# ProPrj_PA_SWITCH_V4_2026-02-15.net
KiCad netlist of a schematic drawn in EasyEDA Pro
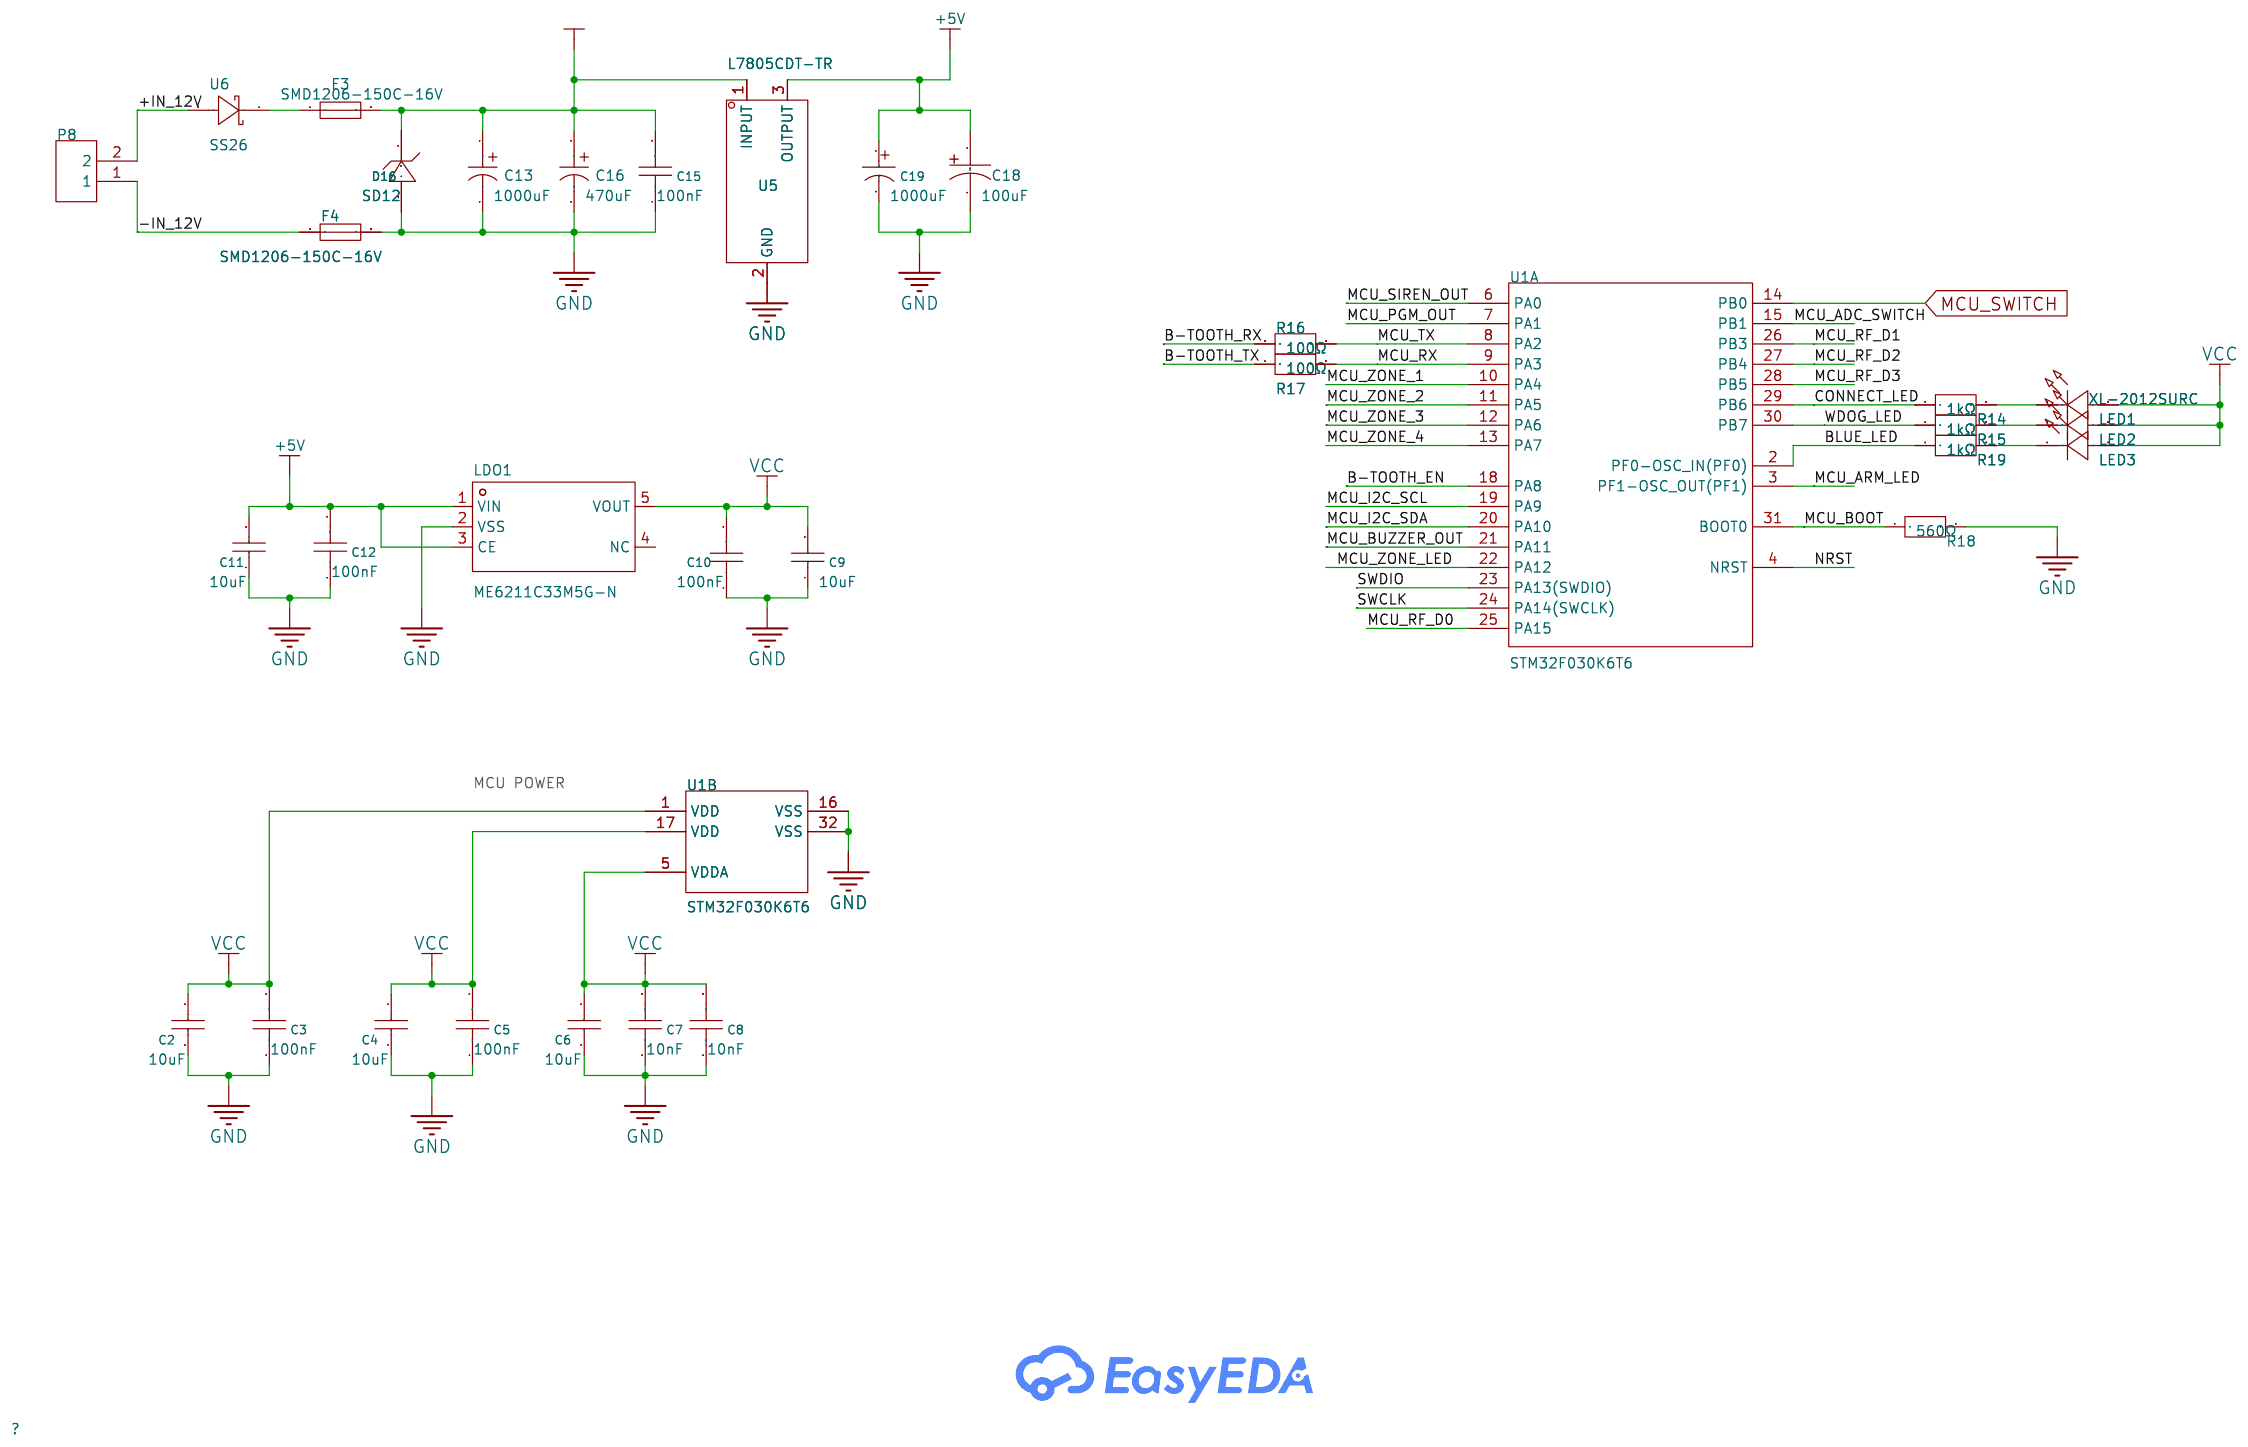
[diagram p0: MCU_POWER]
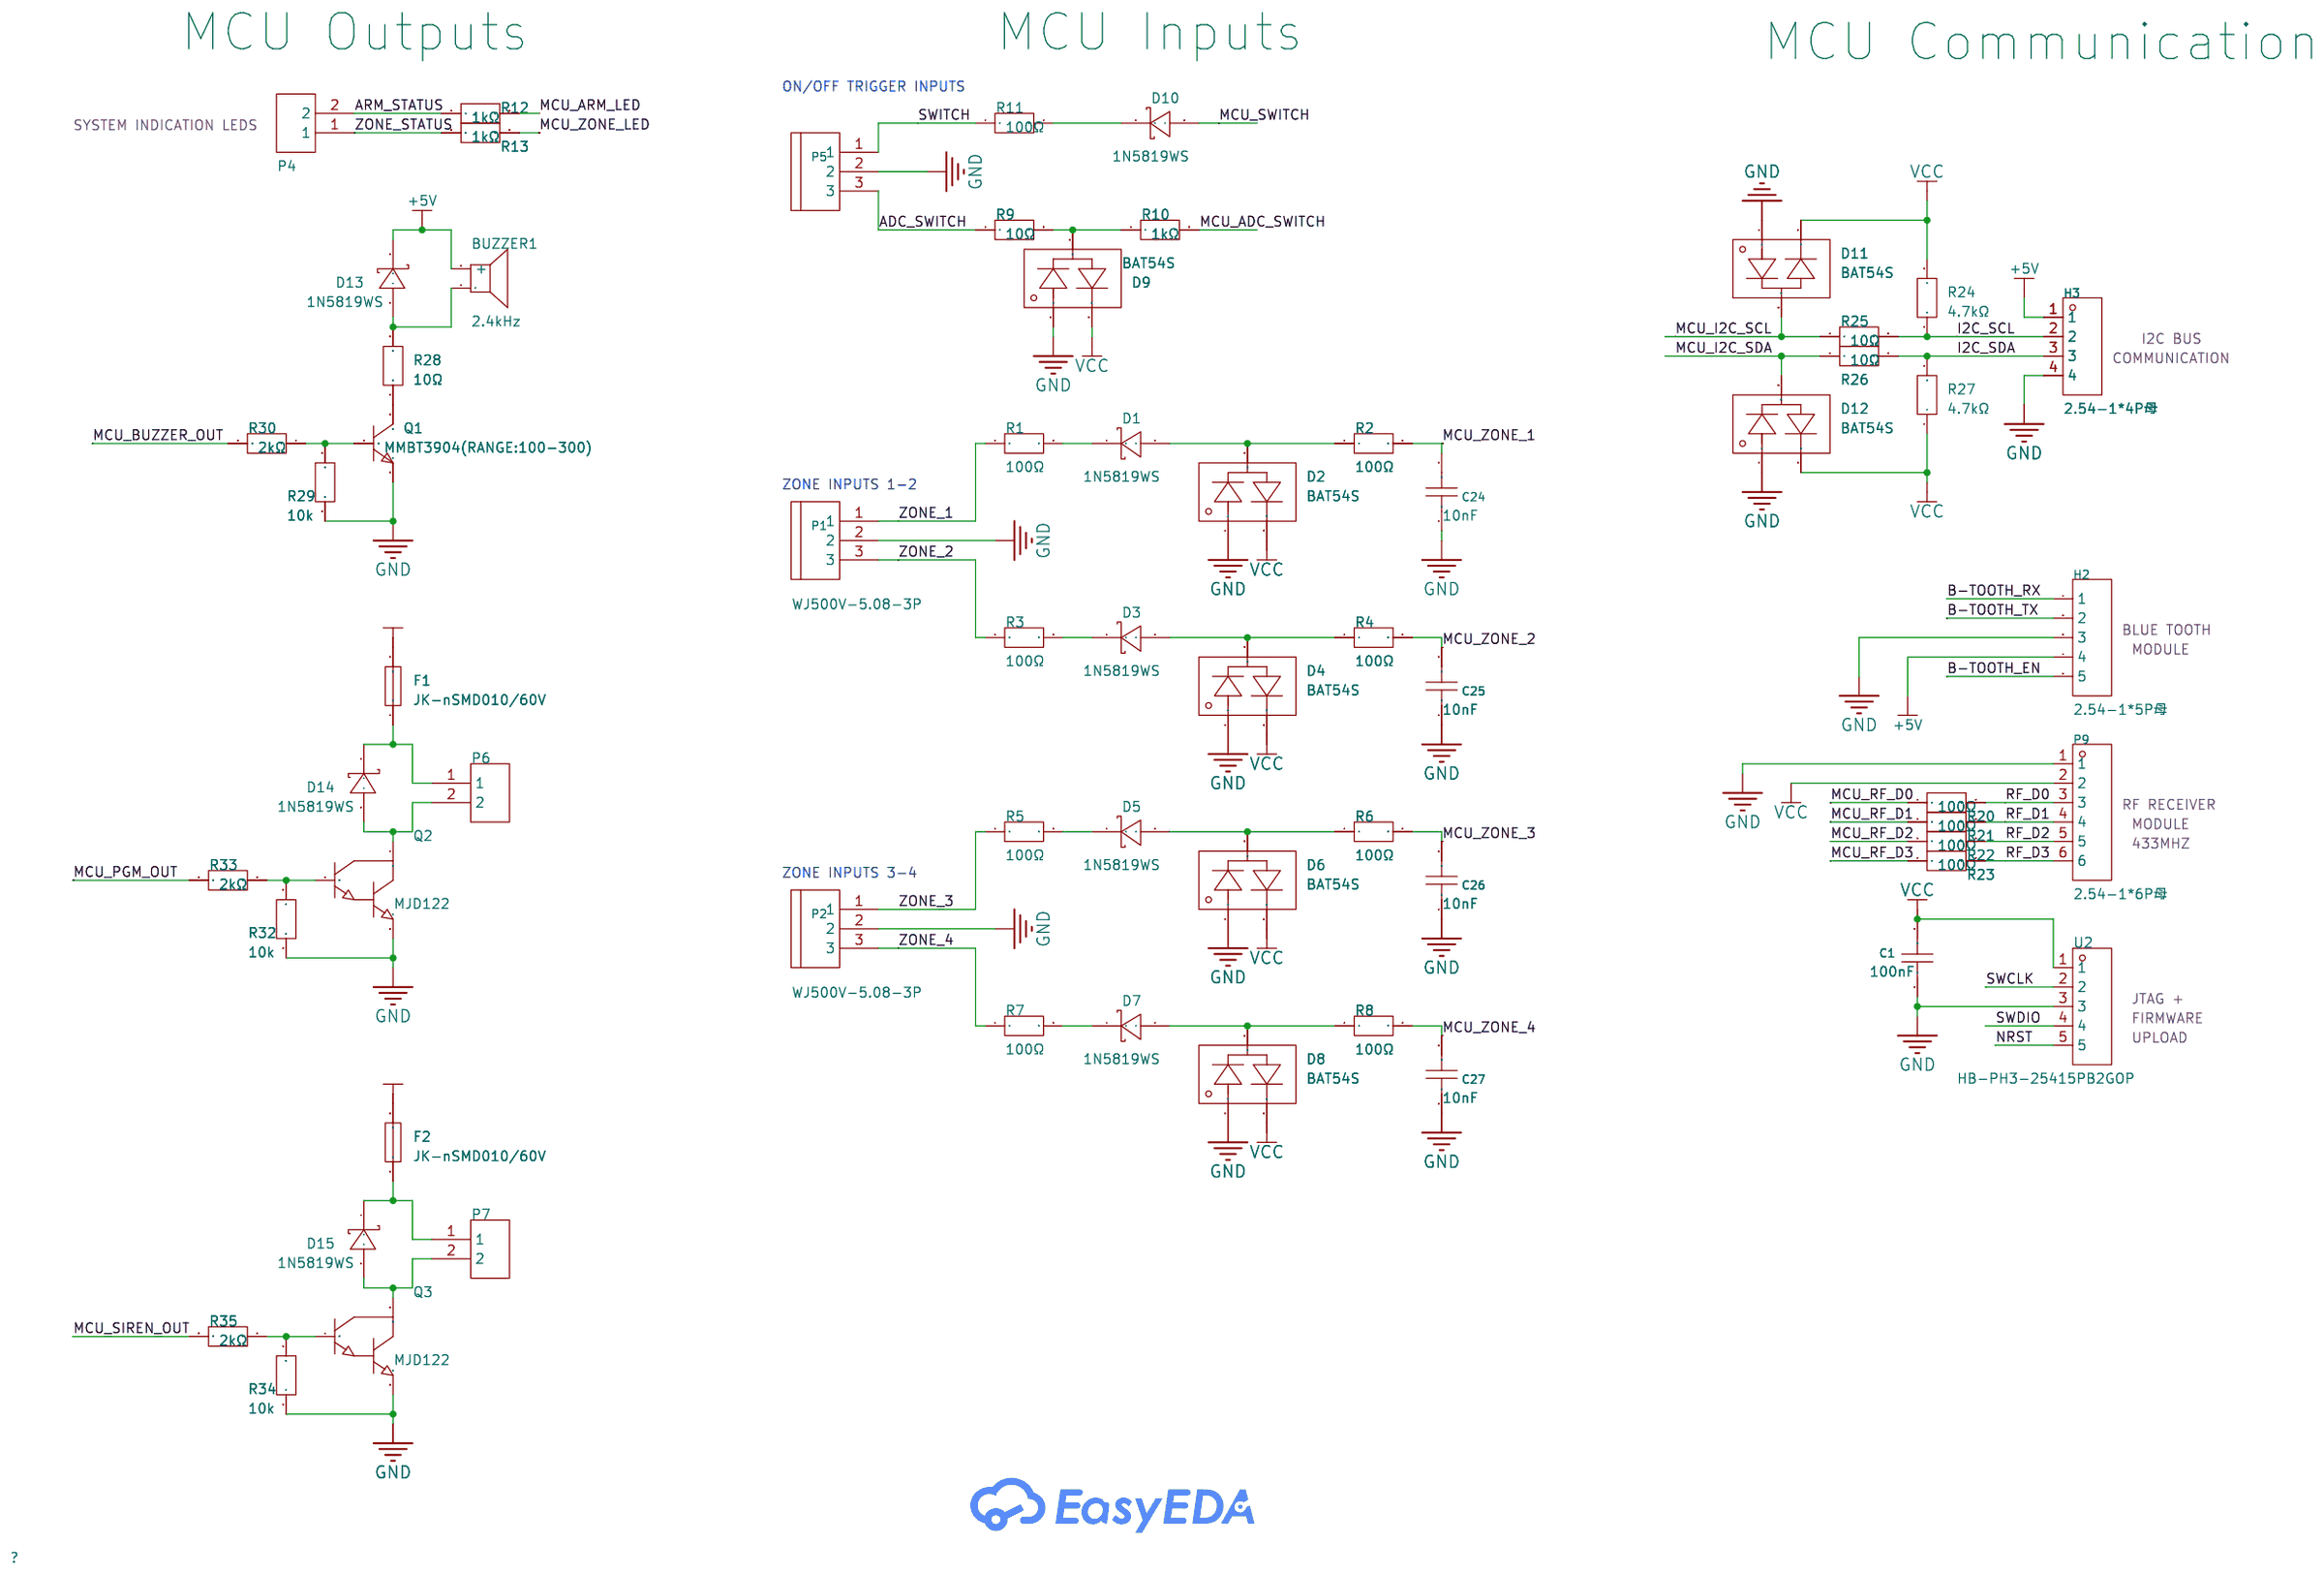
[diagram p1: INPUTS_OUTPUTS]

(export (version "E")
  (design (tool "Eeschema 10.0.6"))
  (components
    (comp (ref "C2")
      (value "10uF")
      (footprint "easyedapro:C0603")
      (fields
        (field (name "Manufacturer Part") "GRM188R60J106ME47D")
        (field (name "Manufacturer") "muRata(村田)")
      )
      (libsource (lib "easyedapro") (part "GRM188R60J106ME47D"))
    )
    (comp (ref "C3")
      (value "100nF")
      (footprint "easyedapro:C0603")
      (fields
        (field (name "Manufacturer Part") "CC0603KRX7R9BB104")
        (field (name "Manufacturer") "YAGEO(国巨)")
      )
      (libsource (lib "easyedapro") (part "CC0603KRX7R9BB104"))
    )
    (comp (ref "C4")
      (value "10uF")
      (footprint "easyedapro:C0603")
      (fields
        (field (name "Manufacturer Part") "GRM188R60J106ME47D")
        (field (name "Manufacturer") "muRata(村田)")
      )
      (libsource (lib "easyedapro") (part "GRM188R60J106ME47D"))
    )
    (comp (ref "C5")
      (value "100nF")
      (footprint "easyedapro:C0603")
      (fields
        (field (name "Manufacturer Part") "CC0603KRX7R9BB104")
        (field (name "Manufacturer") "YAGEO(国巨)")
      )
      (libsource (lib "easyedapro") (part "CC0603KRX7R9BB104"))
    )
    (comp (ref "C6")
      (value "10uF")
      (footprint "easyedapro:C0603")
      (fields
        (field (name "Manufacturer Part") "GRM188R60J106ME47D")
        (field (name "Manufacturer") "muRata(村田)")
      )
      (libsource (lib "easyedapro") (part "GRM188R60J106ME47D"))
    )
    (comp (ref "C7")
      (value "10nF")
      (footprint "easyedapro:C0603")
      (fields
        (field (name "Manufacturer Part") "CC0603KRX7R9BB104")
        (field (name "Manufacturer") "YAGEO(国巨)")
      )
      (libsource (lib "easyedapro") (part "CC0603KRX7R9BB104"))
    )
    (comp (ref "C8")
      (value "10nF")
      (footprint "easyedapro:C0603")
      (fields
        (field (name "Manufacturer Part") "CC0603KRX7R9BB104")
        (field (name "Manufacturer") "YAGEO(国巨)")
      )
      (libsource (lib "easyedapro") (part "CC0603KRX7R9BB104"))
    )
    (comp (ref "C9")
      (value "10uF")
      (footprint "easyedapro:C0603")
      (fields
        (field (name "Manufacturer Part") "GRM188R60J106ME47D")
        (field (name "Manufacturer") "muRata(村田)")
      )
      (libsource (lib "easyedapro") (part "GRM188R60J106ME47D"))
    )
    (comp (ref "C10")
      (value "100nF")
      (footprint "easyedapro:C0603")
      (fields
        (field (name "Manufacturer Part") "CC0603KRX7R9BB104")
        (field (name "Manufacturer") "YAGEO(国巨)")
      )
      (libsource (lib "easyedapro") (part "CC0603KRX7R9BB104"))
    )
    (comp (ref "C11")
      (value "10uF")
      (footprint "easyedapro:C0603")
      (fields
        (field (name "Manufacturer Part") "GRM188R60J106ME47D")
        (field (name "Manufacturer") "muRata(村田)")
      )
      (libsource (lib "easyedapro") (part "GRM188R60J106ME47D"))
    )
    (comp (ref "C12")
      (value "100nF")
      (footprint "easyedapro:C0603")
      (fields
        (field (name "Manufacturer Part") "CC0603KRX7R9BB104")
        (field (name "Manufacturer") "YAGEO(国巨)")
      )
      (libsource (lib "easyedapro") (part "CC0603KRX7R9BB104"))
    )
    (comp (ref "C13")
      (value "1000uF")
      (footprint "easyedapro:CAP-TH_BD10.0-P5.00-D0.6-FD")
      (fields
        (field (name "Manufacturer Part") "CD2881081EM1017VFL")
        (field (name "Manufacturer") "HRK(鸿瑞凯电子)")
      )
      (libsource (lib "easyedapro") (part "CD2881081EM1017VFL"))
    )
    (comp (ref "C15")
      (value "100nF")
      (footprint "easyedapro:C0603")
      (fields
        (field (name "Manufacturer Part") "CC0603KRX7R9BB104")
        (field (name "Manufacturer") "YAGEO(国巨)")
      )
      (libsource (lib "easyedapro") (part "CC0603KRX7R9BB104"))
    )
    (comp (ref "C16")
      (value "470uF")
      (footprint "easyedapro:CAP-TH_BD8.0-P3.50-D0.6-FD_1")
      (fields
        (field (name "Manufacturer Part") "CD2884771EM0812VFL")
        (field (name "Manufacturer") "HRK(鸿瑞凯电子)")
      )
      (libsource (lib "easyedapro") (part "CD2884771EM0812VFL"))
    )
    (comp (ref "C18")
      (value "100uF")
      (footprint "easyedapro:CAP-TH_BD5.0-P2.00-D0.8-FD")
      (fields
        (field (name "Manufacturer Part") "REA101M1ABK-0511P")
        (field (name "Manufacturer") "lelon(立隆)")
      )
      (libsource (lib "easyedapro") (part "REA101M1ABK-0511P"))
    )
    (comp (ref "C19")
      (value "1000uF")
      (footprint "easyedapro:CAP-TH_BD8.0-P3.50-D0.6-FD")
      (fields
        (field (name "Manufacturer Part") "GR108M010F12RR0VL4FP0")
        (field (name "Manufacturer") "CX(承兴)")
      )
      (libsource (lib "easyedapro") (part "1000uF 10V"))
    )
    (comp (ref "D16")
      (value "SD12")
      (footprint "easyedapro:SOD-323_L1.7-W1.3-LS2.7-RD")
      (fields (field (name "Manufacturer") "MDD"))
      (libsource (lib "easyedapro") (part "SD12"))
    )
    (comp (ref "F3")
      (value "SMD1206-150C-16V")
      (footprint "easyedapro:F1206")
      (fields (field (name "Manufacturer") "BNstar(比诺星)"))
      (libsource (lib "easyedapro") (part "SMD1206-150C-16V"))
    )
    (comp (ref "F4")
      (value "SMD1206-150C-16V")
      (footprint "easyedapro:F1206")
      (fields (field (name "Manufacturer") "BNstar(比诺星)"))
      (libsource (lib "easyedapro") (part "SMD1206-150C-16V"))
    )
    (comp (ref "LDO1")
      (value "ME6211C33M5G-N")
      (footprint "easyedapro:SOT-23-5_L3.0-W1.7-P0.95-LS2.8-BL")
      (fields (field (name "Manufacturer") "MICRONE(南京微盟)"))
      (libsource (lib "easyedapro") (part "ME6211C33M5G-N"))
    )
    (comp (ref "LED1")
      (value "XL-2012SURC")
      (footprint "easyedapro:LED0805-R-RD")
      (fields (field (name "Manufacturer") "XINGLIGHT(成兴光)"))
      (libsource (lib "easyedapro") (part "XL-2012SURC"))
    )
    (comp (ref "LED2")
      (value "XL-2012UGC")
      (footprint "easyedapro:LED0805-RD_GREEN")
      (fields (field (name "Manufacturer") "XINGLIGHT(成兴光)"))
      (libsource (lib "easyedapro") (part "XL-2012UGC"))
    )
    (comp (ref "LED3")
      (value "XL-2012UGC")
      (footprint "easyedapro:LED0805-RD_GREEN")
      (fields (field (name "Manufacturer") "XINGLIGHT(成兴光)"))
      (libsource (lib "easyedapro") (part "XL-2012UGC"))
    )
    (comp (ref "P8")
      (value "WJ500V-5.08-2P")
      (footprint "easyedapro:CONN-TH_2P-P5.00_WJ500V-5.08-2P")
      (fields (field (name "Manufacturer") "KANGNEX(康奈克斯电气)"))
      (libsource (lib "easyedapro") (part "WJ500V-5.08-2P-14-00A"))
    )
    (comp (ref "R14")
      (value "1kΩ")
      (footprint "easyedapro:R0603")
      (fields (field (name "Manufacturer Part") "SCR0603J1K") (field (name "Manufacturer") "VO(翔胜)"))
      (libsource (lib "easyedapro") (part "FRC0603J103TS"))
    )
    (comp (ref "R15")
      (value "1kΩ")
      (footprint "easyedapro:R0603")
      (fields (field (name "Manufacturer Part") "SCR0603J1K") (field (name "Manufacturer") "VO(翔胜)"))
      (libsource (lib "easyedapro") (part "FRC0603J103TS"))
    )
    (comp (ref "R16")
      (value "100Ω")
      (footprint "easyedapro:R0603")
      (fields (field (name "Manufacturer Part") "CR0603FA1000G") (field (name "Manufacturer") "LIZ(丽智电子)"))
      (libsource (lib "easyedapro") (part "FRC0603J103TS"))
    )
    (comp (ref "R17")
      (value "100Ω")
      (footprint "easyedapro:R0603")
      (fields (field (name "Manufacturer Part") "CR0603FA1000G") (field (name "Manufacturer") "LIZ(丽智电子)"))
      (libsource (lib "easyedapro") (part "FRC0603J103TS"))
    )
    (comp (ref "R18")
      (value "560Ω")
      (footprint "easyedapro:R0603")
      (fields (field (name "Manufacturer Part") "AECR0603F560RK9") (field (name "Manufacturer") "RESI(开步睿思)"))
      (libsource (lib "easyedapro") (part "FRC0603J103TS"))
    )
    (comp (ref "R19")
      (value "1kΩ")
      (footprint "easyedapro:R0603")
      (fields (field (name "Manufacturer Part") "SCR0603J1K") (field (name "Manufacturer") "VO(翔胜)"))
      (libsource (lib "easyedapro") (part "FRC0603J103TS"))
    )
    (comp (ref "U1")
      (value "STM32F030K6T6")
      (footprint "easyedapro:TQFP-32_L7.0-W7.0-P0.50-BL")
      (fields (field (name "Manufacturer") "ST(意法半导体)"))
      (libsource (lib "easyedapro") (part "STM32F030K6T6"))
    )
    (comp (ref "U5")
      (value "L7805CDT-TR")
      (footprint "easyedapro:TO-252-3_L6.5-W5.8-P4.58-BL")
      (fields (field (name "Manufacturer") "ST(意法半导体)"))
      (libsource (lib "easyedapro") (part "L7805CDT-TR"))
    )
    (comp (ref "U6")
      (value "SS26")
      (footprint "easyedapro:SMA_L4.3-W2.6-LS5.1-RD")
      (fields (field (name "Manufacturer") "ElecSuper(静芯微)"))
      (libsource (lib "easyedapro") (part "SS26_C5350986"))
    )
    (comp (ref "BUZZER1")
      (value "2.4kHz")
      (footprint "easyedapro:BUZ-TH_BD12.0-P7.60-D0.6-FD")
      (fields (field (name "Manufacturer Part") "TMB12A05") (field (name "Manufacturer") "华能"))
      (libsource (lib "easyedapro") (part "TMB12A05"))
    )
    (comp (ref "C1")
      (value "100nF")
      (footprint "easyedapro:C0603")
      (fields
        (field (name "Manufacturer Part") "CC0603KRX7R9BB104")
        (field (name "Manufacturer") "YAGEO(国巨)")
      )
      (libsource (lib "easyedapro") (part "CC0603KRX7R9BB104"))
    )
    (comp (ref "C24")
      (value "10nF")
      (footprint "easyedapro:C0603")
      (fields
        (field (name "Manufacturer Part") "CC0603KRX7R9BB104")
        (field (name "Manufacturer") "YAGEO(国巨)")
      )
      (libsource (lib "easyedapro") (part "CC0603KRX7R9BB104"))
    )
    (comp (ref "C25")
      (value "10nF")
      (footprint "easyedapro:C0603")
      (fields
        (field (name "Manufacturer Part") "CC0603KRX7R9BB104")
        (field (name "Manufacturer") "YAGEO(国巨)")
      )
      (libsource (lib "easyedapro") (part "CC0603KRX7R9BB104"))
    )
    (comp (ref "C26")
      (value "10nF")
      (footprint "easyedapro:C0603")
      (fields
        (field (name "Manufacturer Part") "CC0603KRX7R9BB104")
        (field (name "Manufacturer") "YAGEO(国巨)")
      )
      (libsource (lib "easyedapro") (part "CC0603KRX7R9BB104"))
    )
    (comp (ref "C27")
      (value "10nF")
      (footprint "easyedapro:C0603")
      (fields
        (field (name "Manufacturer Part") "CC0603KRX7R9BB104")
        (field (name "Manufacturer") "YAGEO(国巨)")
      )
      (libsource (lib "easyedapro") (part "CC0603KRX7R9BB104"))
    )
    (comp (ref "D1")
      (value "1N5819WS")
      (footprint "easyedapro:SOD-323_L1.8-W1.3-LS2.5-RD")
      (description "Forward Voltage (Vf@If):600mV@1A Reverse Voltage (Vr):40V Rectified Current:1A")
      (fields (field (name "Manufacturer") "Hottech(合科泰)"))
      (libsource (lib "easyedapro") (part "1N5819WS"))
    )
    (comp (ref "D2")
      (value "BAT54S")
      (footprint "easyedapro:SOT-23-3_L2.9-W1.3-P1.90-LS2.4-BR")
      (fields (field (name "Manufacturer") "Wild Goose(威谷)"))
      (libsource (lib "easyedapro") (part "BAT54S_C22368877"))
    )
    (comp (ref "D3")
      (value "1N5819WS")
      (footprint "easyedapro:SOD-323_L1.8-W1.3-LS2.5-RD")
      (description "Forward Voltage (Vf@If):600mV@1A Reverse Voltage (Vr):40V Rectified Current:1A")
      (fields (field (name "Manufacturer") "Hottech(合科泰)"))
      (libsource (lib "easyedapro") (part "1N5819WS"))
    )
    (comp (ref "D4")
      (value "BAT54S")
      (footprint "easyedapro:SOT-23-3_L2.9-W1.3-P1.90-LS2.4-BR")
      (fields (field (name "Manufacturer") "Wild Goose(威谷)"))
      (libsource (lib "easyedapro") (part "BAT54S_C22368877"))
    )
    (comp (ref "D5")
      (value "1N5819WS")
      (footprint "easyedapro:SOD-323_L1.8-W1.3-LS2.5-RD")
      (description "Forward Voltage (Vf@If):600mV@1A Reverse Voltage (Vr):40V Rectified Current:1A")
      (fields (field (name "Manufacturer") "Hottech(合科泰)"))
      (libsource (lib "easyedapro") (part "1N5819WS"))
    )
    (comp (ref "D6")
      (value "BAT54S")
      (footprint "easyedapro:SOT-23-3_L2.9-W1.3-P1.90-LS2.4-BR")
      (fields (field (name "Manufacturer") "Wild Goose(威谷)"))
      (libsource (lib "easyedapro") (part "BAT54S_C22368877"))
    )
    (comp (ref "D7")
      (value "1N5819WS")
      (footprint "easyedapro:SOD-323_L1.8-W1.3-LS2.5-RD")
      (description "Forward Voltage (Vf@If):600mV@1A Reverse Voltage (Vr):40V Rectified Current:1A")
      (fields (field (name "Manufacturer") "Hottech(合科泰)"))
      (libsource (lib "easyedapro") (part "1N5819WS"))
    )
    (comp (ref "D8")
      (value "BAT54S")
      (footprint "easyedapro:SOT-23-3_L2.9-W1.3-P1.90-LS2.4-BR")
      (fields (field (name "Manufacturer") "Wild Goose(威谷)"))
      (libsource (lib "easyedapro") (part "BAT54S_C22368877"))
    )
    (comp (ref "D9")
      (value "BAT54S")
      (footprint "easyedapro:SOT-23-3_L2.9-W1.3-P1.90-LS2.4-BR")
      (fields (field (name "Manufacturer") "Wild Goose(威谷)"))
      (libsource (lib "easyedapro") (part "BAT54S_C22368877"))
    )
    (comp (ref "D10")
      (value "1N5819WS")
      (footprint "easyedapro:SOD-323_L1.8-W1.3-LS2.5-RD")
      (description "Forward Voltage (Vf@If):600mV@1A Reverse Voltage (Vr):40V Rectified Current:1A")
      (fields (field (name "Manufacturer") "Hottech(合科泰)"))
      (libsource (lib "easyedapro") (part "1N5819WS"))
    )
    (comp (ref "D11")
      (value "BAT54S")
      (footprint "easyedapro:SOT-23-3_L2.9-W1.3-P1.90-LS2.4-BR")
      (fields (field (name "Manufacturer") "Wild Goose(威谷)"))
      (libsource (lib "easyedapro") (part "BAT54S_C22368877"))
    )
    (comp (ref "D12")
      (value "BAT54S")
      (footprint "easyedapro:SOT-23-3_L2.9-W1.3-P1.90-LS2.4-BR")
      (fields (field (name "Manufacturer") "Wild Goose(威谷)"))
      (libsource (lib "easyedapro") (part "BAT54S_C22368877"))
    )
    (comp (ref "D13")
      (value "1N5819WS")
      (footprint "easyedapro:SOD-323_L1.8-W1.3-LS2.5-RD")
      (description "Forward Voltage (Vf@If):600mV@1A Reverse Voltage (Vr):40V Rectified Current:1A")
      (fields (field (name "Manufacturer") "Hottech(合科泰)"))
      (libsource (lib "easyedapro") (part "1N5819WS"))
    )
    (comp (ref "D14")
      (value "1N5819WS")
      (footprint "easyedapro:SOD-323_L1.8-W1.3-LS2.5-RD")
      (description "Forward Voltage (Vf@If):600mV@1A Reverse Voltage (Vr):40V Rectified Current:1A")
      (fields (field (name "Manufacturer") "Hottech(合科泰)"))
      (libsource (lib "easyedapro") (part "1N5819WS"))
    )
    (comp (ref "D15")
      (value "1N5819WS")
      (footprint "easyedapro:SOD-323_L1.8-W1.3-LS2.5-RD")
      (description "Forward Voltage (Vf@If):600mV@1A Reverse Voltage (Vr):40V Rectified Current:1A")
      (fields (field (name "Manufacturer") "Hottech(合科泰)"))
      (libsource (lib "easyedapro") (part "1N5819WS"))
    )
    (comp (ref "F1")
      (value "JK-nSMD010/60V")
      (footprint "easyedapro:F1206")
      (fields (field (name "Manufacturer") "JK(金科)"))
      (libsource (lib "easyedapro") (part "JK-NSMD010/60V"))
    )
    (comp (ref "F2")
      (value "JK-nSMD010/60V")
      (footprint "easyedapro:F1206")
      (fields (field (name "Manufacturer") "JK(金科)"))
      (libsource (lib "easyedapro") (part "JK-NSMD010/60V"))
    )
    (comp (ref "H2")
      (value "2.54-1*5P母")
      (footprint "easyedapro:HDR-TH_5P-P2.54-V-F")
      (fields (field (name "Manufacturer") "BOOMELE(博穆精密)"))
      (libsource (lib "easyedapro") (part "Header-Female-2.54_1x5"))
    )
    (comp (ref "H3")
      (value "2.54-1*4P母")
      (footprint "easyedapro:HDR-TH_4P-P2.54-V-F")
      (fields (field (name "Manufacturer") "BOOMELE(博穆精密)"))
      (libsource (lib "easyedapro") (part "2.54-1*4P母"))
    )
    (comp (ref "P1")
      (value "WJ500V-5.08-3P")
      (footprint "easyedapro:CONN-TH_3P-P5.00_WJ500V-5.08-3P")
      (fields (field (name "Manufacturer") "KANGNEX(康奈克斯电气)"))
      (libsource (lib "easyedapro") (part "WJ500V-5.08-3P-14-00A"))
    )
    (comp (ref "P2")
      (value "WJ500V-5.08-3P")
      (footprint "easyedapro:CONN-TH_3P-P5.00_WJ500V-5.08-3P")
      (fields (field (name "Manufacturer") "KANGNEX(康奈克斯电气)"))
      (libsource (lib "easyedapro") (part "WJ500V-5.08-3P-14-00A"))
    )
    (comp (ref "P4")
      (value "WJ500V-5.08-2P")
      (footprint "easyedapro:CONN-TH_2P-P5.00_WJ500V-5.08-2P")
      (fields (field (name "Manufacturer") "KANGNEX(康奈克斯电气)"))
      (libsource (lib "easyedapro") (part "WJ500V-5.08-2P-14-00A"))
    )
    (comp (ref "P5")
      (value "WJ500V-5.08-3P")
      (footprint "easyedapro:CONN-TH_3P-P5.00_WJ500V-5.08-3P")
      (fields (field (name "Manufacturer") "KANGNEX(康奈克斯电气)"))
      (libsource (lib "easyedapro") (part "WJ500V-5.08-3P-14-00A"))
    )
    (comp (ref "P6")
      (value "WJ500V-5.08-2P")
      (footprint "easyedapro:CONN-TH_2P-P5.00_WJ500V-5.08-2P")
      (fields (field (name "Manufacturer") "KANGNEX(康奈克斯电气)"))
      (libsource (lib "easyedapro") (part "WJ500V-5.08-2P-14-00A"))
    )
    (comp (ref "P7")
      (value "WJ500V-5.08-2P")
      (footprint "easyedapro:CONN-TH_2P-P5.00_WJ500V-5.08-2P")
      (fields (field (name "Manufacturer") "KANGNEX(康奈克斯电气)"))
      (libsource (lib "easyedapro") (part "WJ500V-5.08-2P-14-00A"))
    )
    (comp (ref "P9")
      (value "2.54-1*6P母")
      (footprint "easyedapro:HDR-TH_6P-P2.54-V-F")
      (fields (field (name "Manufacturer") "BOOMELE(博穆精密)"))
      (libsource (lib "easyedapro") (part "Header-Female-2.54_1x6"))
    )
    (comp (ref "Q1")
      (value "MMBT3904(RANGE:100-300)")
      (footprint "easyedapro:SOT-23-3_L2.9-W1.3-P1.90-LS2.4-BR")
      (fields (field (name "Manufacturer") "CJ(江苏长电/长晶)"))
      (libsource (lib "easyedapro") (part "MMBT3904"))
    )
    (comp (ref "Q2")
      (value "MJD122")
      (footprint "easyedapro:TO-252-3_L6.6-W6.1-P4.57-LS9.9-BR-CW")
      (fields (field (name "Manufacturer") "CJ(江苏长电/长晶)"))
      (libsource (lib "easyedapro") (part "MJD122"))
    )
    (comp (ref "Q3")
      (value "MJD122")
      (footprint "easyedapro:TO-252-3_L6.6-W6.1-P4.57-LS9.9-BR-CW")
      (fields (field (name "Manufacturer") "CJ(江苏长电/长晶)"))
      (libsource (lib "easyedapro") (part "MJD122"))
    )
    (comp (ref "R1")
      (value "100Ω")
      (footprint "easyedapro:R0603")
      (fields (field (name "Manufacturer Part") "CR0603FA1000G") (field (name "Manufacturer") "LIZ(丽智电子)"))
      (libsource (lib "easyedapro") (part "FRC0603J103TS"))
    )
    (comp (ref "R2")
      (value "100Ω")
      (footprint "easyedapro:R0603")
      (fields (field (name "Manufacturer Part") "CR0603FA1000G") (field (name "Manufacturer") "LIZ(丽智电子)"))
      (libsource (lib "easyedapro") (part "FRC0603J103TS"))
    )
    (comp (ref "R3")
      (value "100Ω")
      (footprint "easyedapro:R0603")
      (fields (field (name "Manufacturer Part") "CR0603FA1000G") (field (name "Manufacturer") "LIZ(丽智电子)"))
      (libsource (lib "easyedapro") (part "FRC0603J103TS"))
    )
    (comp (ref "R4")
      (value "100Ω")
      (footprint "easyedapro:R0603")
      (fields (field (name "Manufacturer Part") "CR0603FA1000G") (field (name "Manufacturer") "LIZ(丽智电子)"))
      (libsource (lib "easyedapro") (part "FRC0603J103TS"))
    )
    (comp (ref "R5")
      (value "100Ω")
      (footprint "easyedapro:R0603")
      (fields (field (name "Manufacturer Part") "CR0603FA1000G") (field (name "Manufacturer") "LIZ(丽智电子)"))
      (libsource (lib "easyedapro") (part "FRC0603J103TS"))
    )
    (comp (ref "R6")
      (value "100Ω")
      (footprint "easyedapro:R0603")
      (fields (field (name "Manufacturer Part") "CR0603FA1000G") (field (name "Manufacturer") "LIZ(丽智电子)"))
      (libsource (lib "easyedapro") (part "FRC0603J103TS"))
    )
    (comp (ref "R7")
      (value "100Ω")
      (footprint "easyedapro:R0603")
      (fields (field (name "Manufacturer Part") "CR0603FA1000G") (field (name "Manufacturer") "LIZ(丽智电子)"))
      (libsource (lib "easyedapro") (part "FRC0603J103TS"))
    )
    (comp (ref "R8")
      (value "100Ω")
      (footprint "easyedapro:R0603")
      (fields (field (name "Manufacturer Part") "CR0603FA1000G") (field (name "Manufacturer") "LIZ(丽智电子)"))
      (libsource (lib "easyedapro") (part "FRC0603J103TS"))
    )
    (comp (ref "R9")
      (value "10Ω")
      (footprint "easyedapro:R0603")
      (fields (field (name "Manufacturer Part") "SCR0603J10R") (field (name "Manufacturer") "VO(翔胜)"))
      (libsource (lib "easyedapro") (part "FRC0603J103TS"))
    )
    (comp (ref "R10")
      (value "1kΩ")
      (footprint "easyedapro:R0603")
      (fields (field (name "Manufacturer Part") "SCR0603J1K") (field (name "Manufacturer") "VO(翔胜)"))
      (libsource (lib "easyedapro") (part "FRC0603J103TS"))
    )
    (comp (ref "R11")
      (value "100Ω")
      (footprint "easyedapro:R0603")
      (fields (field (name "Manufacturer Part") "CR0603FA1000G") (field (name "Manufacturer") "LIZ(丽智电子)"))
      (libsource (lib "easyedapro") (part "FRC0603J103TS"))
    )
    (comp (ref "R12")
      (value "1kΩ")
      (footprint "easyedapro:R0603")
      (fields (field (name "Manufacturer Part") "SCR0603J1K") (field (name "Manufacturer") "VO(翔胜)"))
      (libsource (lib "easyedapro") (part "FRC0603J103TS"))
    )
    (comp (ref "R13")
      (value "1kΩ")
      (footprint "easyedapro:R0603")
      (fields (field (name "Manufacturer Part") "SCR0603J1K") (field (name "Manufacturer") "VO(翔胜)"))
      (libsource (lib "easyedapro") (part "FRC0603J103TS"))
    )
    (comp (ref "R20")
      (value "100Ω")
      (footprint "easyedapro:R0603")
      (fields (field (name "Manufacturer Part") "CR0603FA1000G") (field (name "Manufacturer") "LIZ(丽智电子)"))
      (libsource (lib "easyedapro") (part "FRC0603J103TS"))
    )
    (comp (ref "R21")
      (value "100Ω")
      (footprint "easyedapro:R0603")
      (fields (field (name "Manufacturer Part") "CR0603FA1000G") (field (name "Manufacturer") "LIZ(丽智电子)"))
      (libsource (lib "easyedapro") (part "FRC0603J103TS"))
    )
    (comp (ref "R22")
      (value "100Ω")
      (footprint "easyedapro:R0603")
      (fields (field (name "Manufacturer Part") "CR0603FA1000G") (field (name "Manufacturer") "LIZ(丽智电子)"))
      (libsource (lib "easyedapro") (part "FRC0603J103TS"))
    )
    (comp (ref "R23")
      (value "100Ω")
      (footprint "easyedapro:R0603")
      (fields (field (name "Manufacturer Part") "CR0603FA1000G") (field (name "Manufacturer") "LIZ(丽智电子)"))
      (libsource (lib "easyedapro") (part "FRC0603J103TS"))
    )
    (comp (ref "R24")
      (value "4.7kΩ")
      (footprint "easyedapro:R0603")
      (fields (field (name "Manufacturer Part") "CR0603FA4701G") (field (name "Manufacturer") "LIZ(丽智电子)"))
      (libsource (lib "easyedapro") (part "FRC0603J103TS"))
    )
    (comp (ref "R25")
      (value "10Ω")
      (footprint "easyedapro:R0603")
      (fields (field (name "Manufacturer Part") "SCR0603J10R") (field (name "Manufacturer") "VO(翔胜)"))
      (libsource (lib "easyedapro") (part "FRC0603J103TS"))
    )
    (comp (ref "R26")
      (value "10Ω")
      (footprint "easyedapro:R0603")
      (fields (field (name "Manufacturer Part") "SCR0603J10R") (field (name "Manufacturer") "VO(翔胜)"))
      (libsource (lib "easyedapro") (part "FRC0603J103TS"))
    )
    (comp (ref "R27")
      (value "4.7kΩ")
      (footprint "easyedapro:R0603")
      (fields (field (name "Manufacturer Part") "CR0603FA4701G") (field (name "Manufacturer") "LIZ(丽智电子)"))
      (libsource (lib "easyedapro") (part "FRC0603J103TS"))
    )
    (comp (ref "R28")
      (value "10Ω")
      (footprint "easyedapro:R0603")
      (fields (field (name "Manufacturer Part") "SCR0603J10R") (field (name "Manufacturer") "VO(翔胜)"))
      (libsource (lib "easyedapro") (part "FRC0603J103TS"))
    )
    (comp (ref "R29")
      (value "10kΩ")
      (footprint "easyedapro:R0603")
      (fields (field (name "Manufacturer Part") "FRC0603J103TS") (field (name "Manufacturer") "FOJAN(富捷)"))
      (libsource (lib "easyedapro") (part "FRC0603J103TS"))
    )
    (comp (ref "R30")
      (value "2kΩ")
      (footprint "easyedapro:R0603")
      (fields (field (name "Manufacturer Part") "SCR0603F2K") (field (name "Manufacturer") "VO(翔胜)"))
      (libsource (lib "easyedapro") (part "FRC0603J103TS"))
    )
    (comp (ref "R32")
      (value "10kΩ")
      (footprint "easyedapro:R0603")
      (fields (field (name "Manufacturer Part") "FRC0603J103TS") (field (name "Manufacturer") "FOJAN(富捷)"))
      (libsource (lib "easyedapro") (part "FRC0603J103TS"))
    )
    (comp (ref "R33")
      (value "2kΩ")
      (footprint "easyedapro:R0603")
      (fields (field (name "Manufacturer Part") "SCR0603F2K") (field (name "Manufacturer") "VO(翔胜)"))
      (libsource (lib "easyedapro") (part "FRC0603J103TS"))
    )
    (comp (ref "R34")
      (value "10kΩ")
      (footprint "easyedapro:R0603")
      (fields (field (name "Manufacturer Part") "FRC0603J103TS") (field (name "Manufacturer") "FOJAN(富捷)"))
      (libsource (lib "easyedapro") (part "FRC0603J103TS"))
    )
    (comp (ref "R35")
      (value "2kΩ")
      (footprint "easyedapro:R0603")
      (fields (field (name "Manufacturer Part") "SCR0603F2K") (field (name "Manufacturer") "VO(翔胜)"))
      (libsource (lib "easyedapro") (part "FRC0603J103TS"))
    )
    (comp (ref "U2")
      (value "HB-PH3-25415PB2GOP")
      (footprint "easyedapro:HDR-TH_5P-P2.54-V-M")
      (fields (field (name "Manufacturer") "HANBO(汉博)"))
      (libsource (lib "easyedapro") (part "HB-PH3-25415PB2GOP"))
    )
  )
  (nets
    (net (code "1") (name "+5V") (class "Default")
      (node (ref "BUZZER1") (pin "1") (pinfunction "+_1") (pintype "unspecified"))
      (node (ref "C11") (pin "2") (pinfunction "2_2") (pintype "input"))
      (node (ref "C12") (pin "2") (pinfunction "2_2") (pintype "input"))
      (node (ref "C18") (pin "1") (pinfunction "1_1") (pintype "unspecified"))
      (node (ref "C19") (pin "1") (pinfunction "1_1") (pintype "input"))
      (node (ref "D13") (pin "1") (pinfunction "K_1") (pintype "unspecified"))
      (node (ref "H2") (pin "4") (pinfunction "4_4") (pintype "input"))
      (node (ref "H3") (pin "1") (pinfunction "1_1") (pintype "input"))
      (node (ref "LDO1") (pin "1") (pinfunction "VIN_1") (pintype "input"))
      (node (ref "LDO1") (pin "3") (pinfunction "CE_3") (pintype "input"))
      (node (ref "U5") (pin "3") (pinfunction "OUTPUT_3") (pintype "unspecified"))
    )
    (net (code "2") (name "+12V") (class "Default")
      (node (ref "C13") (pin "1") (pinfunction "1_1") (pintype "input"))
      (node (ref "C15") (pin "2") (pinfunction "2_2") (pintype "input"))
      (node (ref "C16") (pin "1") (pinfunction "1_1") (pintype "input"))
      (node (ref "D16") (pin "1") (pinfunction "C_1") (pintype "input"))
      (node (ref "F1") (pin "2") (pinfunction "2_2") (pintype "unspecified"))
      (node (ref "F2") (pin "2") (pinfunction "2_2") (pintype "unspecified"))
      (node (ref "F3") (pin "2") (pinfunction "2_2") (pintype "input"))
      (node (ref "U5") (pin "1") (pinfunction "INPUT_1") (pintype "unspecified"))
    )
    (net (code "3") (name "+IN_12V") (class "Default")
      (node (ref "P8") (pin "2") (pinfunction "2_2") (pintype "unspecified"))
      (node (ref "U6") (pin "2") (pinfunction "A_2") (pintype "unspecified"))
    )
    (net (code "4") (name "-IN_12V") (class "Default")
      (node (ref "F4") (pin "1") (pinfunction "1_1") (pintype "input"))
      (node (ref "P8") (pin "1") (pinfunction "1_1") (pintype "unspecified"))
    )
    (net (code "5") (name "ADC_SWITCH") (class "Default")
      (node (ref "P5") (pin "3") (pinfunction "3_3") (pintype "input"))
      (node (ref "R9") (pin "1") (pinfunction "1_1") (pintype "unspecified"))
    )
    (net (code "6") (name "ARM_STATUS") (class "Default")
      (node (ref "P4") (pin "2") (pinfunction "2_2") (pintype "unspecified"))
      (node (ref "R12") (pin "1") (pinfunction "1_1") (pintype "unspecified"))
    )
    (net (code "7") (name "B-TOOTH_EN") (class "Default")
      (node (ref "H2") (pin "5") (pinfunction "5_5") (pintype "input"))
      (node (ref "U1") (pin "18") (pinfunction "PA8_18") (pintype "bidirectional"))
    )
    (net (code "8") (name "B-TOOTH_RX") (class "Default")
      (node (ref "H2") (pin "1") (pinfunction "1_1") (pintype "input"))
      (node (ref "R16") (pin "1") (pinfunction "1_1") (pintype "unspecified"))
    )
    (net (code "9") (name "B-TOOTH_TX") (class "Default")
      (node (ref "H2") (pin "2") (pinfunction "2_2") (pintype "input"))
      (node (ref "R17") (pin "1") (pinfunction "1_1") (pintype "unspecified"))
    )
    (net (code "10") (name "BLUE_LED") (class "Default")
      (node (ref "R19") (pin "1") (pinfunction "1_1") (pintype "unspecified"))
      (node (ref "U1") (pin "2") (pinfunction "PF0-OSC_IN(PF0)_2") (pintype "bidirectional"))
    )
    (net (code "11") (name "CONNECT_LED") (class "Default")
      (node (ref "R14") (pin "1") (pinfunction "1_1") (pintype "unspecified"))
      (node (ref "U1") (pin "29") (pinfunction "PB6_29") (pintype "bidirectional"))
    )
    (net (code "12") (name "GND") (class "Default")
      (node (ref "C1") (pin "1") (pinfunction "1_1") (pintype "input"))
      (node (ref "C10") (pin "1") (pinfunction "1_1") (pintype "input"))
      (node (ref "C11") (pin "1") (pinfunction "1_1") (pintype "input"))
      (node (ref "C12") (pin "1") (pinfunction "1_1") (pintype "input"))
      (node (ref "C13") (pin "2") (pinfunction "2_2") (pintype "input"))
      (node (ref "C15") (pin "1") (pinfunction "1_1") (pintype "input"))
      (node (ref "C16") (pin "2") (pinfunction "2_2") (pintype "input"))
      (node (ref "C18") (pin "2") (pinfunction "2_2") (pintype "unspecified"))
      (node (ref "C19") (pin "2") (pinfunction "2_2") (pintype "input"))
      (node (ref "C2") (pin "1") (pinfunction "1_1") (pintype "input"))
      (node (ref "C24") (pin "1") (pinfunction "1_1") (pintype "input"))
      (node (ref "C25") (pin "1") (pinfunction "1_1") (pintype "input"))
      (node (ref "C26") (pin "1") (pinfunction "1_1") (pintype "input"))
      (node (ref "C27") (pin "1") (pinfunction "1_1") (pintype "input"))
      (node (ref "C3") (pin "1") (pinfunction "1_1") (pintype "input"))
      (node (ref "C4") (pin "1") (pinfunction "1_1") (pintype "input"))
      (node (ref "C5") (pin "1") (pinfunction "1_1") (pintype "input"))
      (node (ref "C6") (pin "1") (pinfunction "1_1") (pintype "input"))
      (node (ref "C7") (pin "1") (pinfunction "1_1") (pintype "input"))
      (node (ref "C8") (pin "1") (pinfunction "1_1") (pintype "input"))
      (node (ref "C9") (pin "1") (pinfunction "1_1") (pintype "input"))
      (node (ref "D11") (pin "1") (pinfunction "1_1") (pintype "unspecified"))
      (node (ref "D12") (pin "1") (pinfunction "1_1") (pintype "unspecified"))
      (node (ref "D16") (pin "2") (pinfunction "A_2") (pintype "input"))
      (node (ref "D2") (pin "1") (pinfunction "1_1") (pintype "unspecified"))
      (node (ref "D4") (pin "1") (pinfunction "1_1") (pintype "unspecified"))
      (node (ref "D6") (pin "1") (pinfunction "1_1") (pintype "unspecified"))
      (node (ref "D8") (pin "1") (pinfunction "1_1") (pintype "unspecified"))
      (node (ref "D9") (pin "1") (pinfunction "1_1") (pintype "unspecified"))
      (node (ref "F4") (pin "2") (pinfunction "2_2") (pintype "input"))
      (node (ref "H2") (pin "3") (pinfunction "3_3") (pintype "input"))
      (node (ref "H3") (pin "4") (pinfunction "4_4") (pintype "input"))
      (node (ref "LDO1") (pin "2") (pinfunction "VSS_2") (pintype "input"))
      (node (ref "P1") (pin "2") (pinfunction "2_2") (pintype "input"))
      (node (ref "P2") (pin "2") (pinfunction "2_2") (pintype "input"))
      (node (ref "P5") (pin "2") (pinfunction "2_2") (pintype "input"))
      (node (ref "P9") (pin "1") (pinfunction "1_1") (pintype "input"))
      (node (ref "Q1") (pin "2") (pinfunction "E_2") (pintype "unspecified"))
      (node (ref "Q2") (pin "3") (pinfunction "E_3") (pintype "unspecified"))
      (node (ref "Q3") (pin "3") (pinfunction "E_3") (pintype "unspecified"))
      (node (ref "R18") (pin "2") (pinfunction "2_2") (pintype "unspecified"))
      (node (ref "R29") (pin "1") (pinfunction "1_1") (pintype "unspecified"))
      (node (ref "R32") (pin "1") (pinfunction "1_1") (pintype "unspecified"))
      (node (ref "R34") (pin "1") (pinfunction "1_1") (pintype "unspecified"))
      (node (ref "U1") (pin "16") (pinfunction "VSS_16") (pintype "unspecified"))
      (node (ref "U1") (pin "32") (pinfunction "VSS_32") (pintype "unspecified"))
      (node (ref "U2") (pin "3") (pinfunction "3_3") (pintype "unspecified"))
      (node (ref "U5") (pin "2") (pinfunction "GND_2") (pintype "unspecified"))
    )
    (net (code "13") (name "I2C_SCL") (class "Default")
      (node (ref "H3") (pin "2") (pinfunction "2_2") (pintype "input"))
      (node (ref "R24") (pin "1") (pinfunction "1_1") (pintype "unspecified"))
      (node (ref "R25") (pin "2") (pinfunction "2_2") (pintype "unspecified"))
    )
    (net (code "14") (name "I2C_SDA") (class "Default")
      (node (ref "H3") (pin "3") (pinfunction "3_3") (pintype "input"))
      (node (ref "R26") (pin "2") (pinfunction "2_2") (pintype "unspecified"))
      (node (ref "R27") (pin "2") (pinfunction "2_2") (pintype "unspecified"))
    )
    (net (code "15") (name "MCU_ADC_SWITCH") (class "Default")
      (node (ref "R10") (pin "2") (pinfunction "2_2") (pintype "unspecified"))
      (node (ref "U1") (pin "15") (pinfunction "PB1_15") (pintype "bidirectional"))
    )
    (net (code "16") (name "MCU_ARM_LED") (class "Default")
      (node (ref "R12") (pin "2") (pinfunction "2_2") (pintype "unspecified"))
      (node (ref "U1") (pin "3") (pinfunction "PF1-OSC_OUT(PF1)_3") (pintype "bidirectional"))
    )
    (net (code "17") (name "MCU_BOOT") (class "Default")
      (node (ref "R18") (pin "1") (pinfunction "1_1") (pintype "unspecified"))
      (node (ref "U1") (pin "31") (pinfunction "BOOT0_31") (pintype "unspecified"))
    )
    (net (code "18") (name "MCU_BUZZER_OUT") (class "Default")
      (node (ref "R30") (pin "2") (pinfunction "2_2") (pintype "unspecified"))
      (node (ref "U1") (pin "21") (pinfunction "PA11_21") (pintype "bidirectional"))
    )
    (net (code "19") (name "MCU_I2C_SCL") (class "Default")
      (node (ref "D11") (pin "3") (pinfunction "3_3") (pintype "unspecified"))
      (node (ref "R25") (pin "1") (pinfunction "1_1") (pintype "unspecified"))
      (node (ref "U1") (pin "19") (pinfunction "PA9_19") (pintype "bidirectional"))
    )
    (net (code "20") (name "MCU_I2C_SDA") (class "Default")
      (node (ref "D12") (pin "3") (pinfunction "3_3") (pintype "unspecified"))
      (node (ref "R26") (pin "1") (pinfunction "1_1") (pintype "unspecified"))
      (node (ref "U1") (pin "20") (pinfunction "PA10_20") (pintype "bidirectional"))
    )
    (net (code "21") (name "MCU_PGM_OUT") (class "Default")
      (node (ref "R33") (pin "2") (pinfunction "2_2") (pintype "unspecified"))
      (node (ref "U1") (pin "7") (pinfunction "PA1_7") (pintype "bidirectional"))
    )
    (net (code "22") (name "MCU_RF_D0") (class "Default")
      (node (ref "R20") (pin "1") (pinfunction "1_1") (pintype "unspecified"))
      (node (ref "U1") (pin "25") (pinfunction "PA15_25") (pintype "bidirectional"))
    )
    (net (code "23") (name "MCU_RF_D1") (class "Default")
      (node (ref "R21") (pin "1") (pinfunction "1_1") (pintype "unspecified"))
      (node (ref "U1") (pin "26") (pinfunction "PB3_26") (pintype "bidirectional"))
    )
    (net (code "24") (name "MCU_RF_D2") (class "Default")
      (node (ref "R22") (pin "1") (pinfunction "1_1") (pintype "unspecified"))
      (node (ref "U1") (pin "27") (pinfunction "PB4_27") (pintype "bidirectional"))
    )
    (net (code "25") (name "MCU_RF_D3") (class "Default")
      (node (ref "R23") (pin "1") (pinfunction "1_1") (pintype "unspecified"))
      (node (ref "U1") (pin "28") (pinfunction "PB5_28") (pintype "bidirectional"))
    )
    (net (code "26") (name "MCU_RX") (class "Default")
      (node (ref "R17") (pin "2") (pinfunction "2_2") (pintype "unspecified"))
      (node (ref "U1") (pin "9") (pinfunction "PA3_9") (pintype "bidirectional"))
    )
    (net (code "27") (name "MCU_SIREN_OUT") (class "Default")
      (node (ref "R35") (pin "2") (pinfunction "2_2") (pintype "unspecified"))
      (node (ref "U1") (pin "6") (pinfunction "PA0_6") (pintype "bidirectional"))
    )
    (net (code "28") (name "MCU_SWITCH") (class "Default")
      (node (ref "D10") (pin "2") (pinfunction "A_2") (pintype "unspecified"))
      (node (ref "U1") (pin "14") (pinfunction "PB0_14") (pintype "bidirectional"))
    )
    (net (code "29") (name "MCU_TX") (class "Default")
      (node (ref "R16") (pin "2") (pinfunction "2_2") (pintype "unspecified"))
      (node (ref "U1") (pin "8") (pinfunction "PA2_8") (pintype "bidirectional"))
    )
    (net (code "30") (name "MCU_ZONE_1") (class "Default")
      (node (ref "C24") (pin "2") (pinfunction "2_2") (pintype "input"))
      (node (ref "R2") (pin "2") (pinfunction "2_2") (pintype "unspecified"))
      (node (ref "U1") (pin "10") (pinfunction "PA4_10") (pintype "bidirectional"))
    )
    (net (code "31") (name "MCU_ZONE_2") (class "Default")
      (node (ref "C25") (pin "2") (pinfunction "2_2") (pintype "input"))
      (node (ref "R4") (pin "2") (pinfunction "2_2") (pintype "unspecified"))
      (node (ref "U1") (pin "11") (pinfunction "PA5_11") (pintype "bidirectional"))
    )
    (net (code "32") (name "MCU_ZONE_3") (class "Default")
      (node (ref "C26") (pin "2") (pinfunction "2_2") (pintype "input"))
      (node (ref "R6") (pin "2") (pinfunction "2_2") (pintype "unspecified"))
      (node (ref "U1") (pin "12") (pinfunction "PA6_12") (pintype "bidirectional"))
    )
    (net (code "33") (name "MCU_ZONE_4") (class "Default")
      (node (ref "C27") (pin "2") (pinfunction "2_2") (pintype "input"))
      (node (ref "R8") (pin "2") (pinfunction "2_2") (pintype "unspecified"))
      (node (ref "U1") (pin "13") (pinfunction "PA7_13") (pintype "bidirectional"))
    )
    (net (code "34") (name "MCU_ZONE_LED") (class "Default")
      (node (ref "R13") (pin "2") (pinfunction "2_2") (pintype "unspecified"))
      (node (ref "U1") (pin "22") (pinfunction "PA12_22") (pintype "bidirectional"))
    )
    (net (code "35") (name "NRST") (class "Default")
      (node (ref "U1") (pin "4") (pinfunction "NRST_4") (pintype "bidirectional"))
      (node (ref "U2") (pin "5") (pinfunction "5_5") (pintype "unspecified"))
    )
    (net (code "36") (name "Net-(D1-A)") (class "Default")
      (node (ref "D1") (pin "2") (pinfunction "A_2") (pintype "unspecified"))
      (node (ref "D2") (pin "3") (pinfunction "3_3") (pintype "unspecified"))
      (node (ref "R2") (pin "1") (pinfunction "1_1") (pintype "unspecified"))
    )
    (net (code "37") (name "Net-(D1-K)") (class "Default")
      (node (ref "D1") (pin "1") (pinfunction "K_1") (pintype "unspecified"))
      (node (ref "R1") (pin "2") (pinfunction "2_2") (pintype "unspecified"))
    )
    (net (code "38") (name "Net-(D3-A)") (class "Default")
      (node (ref "D3") (pin "2") (pinfunction "A_2") (pintype "unspecified"))
      (node (ref "D4") (pin "3") (pinfunction "3_3") (pintype "unspecified"))
      (node (ref "R4") (pin "1") (pinfunction "1_1") (pintype "unspecified"))
    )
    (net (code "39") (name "Net-(D3-K)") (class "Default")
      (node (ref "D3") (pin "1") (pinfunction "K_1") (pintype "unspecified"))
      (node (ref "R3") (pin "2") (pinfunction "2_2") (pintype "unspecified"))
    )
    (net (code "40") (name "Net-(D5-A)") (class "Default")
      (node (ref "D5") (pin "2") (pinfunction "A_2") (pintype "unspecified"))
      (node (ref "D6") (pin "3") (pinfunction "3_3") (pintype "unspecified"))
      (node (ref "R6") (pin "1") (pinfunction "1_1") (pintype "unspecified"))
    )
    (net (code "41") (name "Net-(D5-K)") (class "Default")
      (node (ref "D5") (pin "1") (pinfunction "K_1") (pintype "unspecified"))
      (node (ref "R5") (pin "2") (pinfunction "2_2") (pintype "unspecified"))
    )
    (net (code "42") (name "Net-(D7-A)") (class "Default")
      (node (ref "D7") (pin "2") (pinfunction "A_2") (pintype "unspecified"))
      (node (ref "D8") (pin "3") (pinfunction "3_3") (pintype "unspecified"))
      (node (ref "R8") (pin "1") (pinfunction "1_1") (pintype "unspecified"))
    )
    (net (code "43") (name "Net-(D7-K)") (class "Default")
      (node (ref "D7") (pin "1") (pinfunction "K_1") (pintype "unspecified"))
      (node (ref "R7") (pin "2") (pinfunction "2_2") (pintype "unspecified"))
    )
    (net (code "44") (name "Net-(D9-Pad3)") (class "Default")
      (node (ref "D9") (pin "3") (pinfunction "3_3") (pintype "unspecified"))
      (node (ref "R10") (pin "1") (pinfunction "1_1") (pintype "unspecified"))
      (node (ref "R9") (pin "2") (pinfunction "2_2") (pintype "unspecified"))
    )
    (net (code "45") (name "Net-(D10-K)") (class "Default")
      (node (ref "D10") (pin "1") (pinfunction "K_1") (pintype "unspecified"))
      (node (ref "R11") (pin "2") (pinfunction "2_2") (pintype "unspecified"))
    )
    (net (code "46") (name "Net-(D13-A)") (class "Default")
      (node (ref "BUZZER1") (pin "2") (pinfunction "2_2") (pintype "unspecified"))
      (node (ref "D13") (pin "2") (pinfunction "A_2") (pintype "unspecified"))
      (node (ref "R28") (pin "2") (pinfunction "2_2") (pintype "unspecified"))
    )
    (net (code "47") (name "Net-(D14-A)") (class "Default")
      (node (ref "D14") (pin "2") (pinfunction "A_2") (pintype "unspecified"))
      (node (ref "P6") (pin "2") (pinfunction "2_2") (pintype "unspecified"))
      (node (ref "Q2") (pin "2") (pinfunction "C_2") (pintype "unspecified"))
    )
    (net (code "48") (name "Net-(D14-K)") (class "Default")
      (node (ref "D14") (pin "1") (pinfunction "K_1") (pintype "unspecified"))
      (node (ref "F1") (pin "1") (pinfunction "1_1") (pintype "unspecified"))
      (node (ref "P6") (pin "1") (pinfunction "1_1") (pintype "unspecified"))
    )
    (net (code "49") (name "Net-(D15-A)") (class "Default")
      (node (ref "D15") (pin "2") (pinfunction "A_2") (pintype "unspecified"))
      (node (ref "P7") (pin "2") (pinfunction "2_2") (pintype "unspecified"))
      (node (ref "Q3") (pin "2") (pinfunction "C_2") (pintype "unspecified"))
    )
    (net (code "50") (name "Net-(D15-K)") (class "Default")
      (node (ref "D15") (pin "1") (pinfunction "K_1") (pintype "unspecified"))
      (node (ref "F2") (pin "1") (pinfunction "1_1") (pintype "unspecified"))
      (node (ref "P7") (pin "1") (pinfunction "1_1") (pintype "unspecified"))
    )
    (net (code "51") (name "Net-(LED1-K)") (class "Default")
      (node (ref "LED1") (pin "2") (pinfunction "K_2") (pintype "unspecified"))
      (node (ref "R14") (pin "2") (pinfunction "2_2") (pintype "unspecified"))
    )
    (net (code "52") (name "Net-(LED2-K)") (class "Default")
      (node (ref "LED2") (pin "1") (pinfunction "K_1") (pintype "unspecified"))
      (node (ref "R15") (pin "2") (pinfunction "2_2") (pintype "unspecified"))
    )
    (net (code "53") (name "Net-(LED3-K)") (class "Default")
      (node (ref "LED3") (pin "1") (pinfunction "K_1") (pintype "unspecified"))
      (node (ref "R19") (pin "2") (pinfunction "2_2") (pintype "unspecified"))
    )
    (net (code "54") (name "Net-(Q1-B)") (class "Default")
      (node (ref "Q1") (pin "1") (pinfunction "B_1") (pintype "unspecified"))
      (node (ref "R29") (pin "2") (pinfunction "2_2") (pintype "unspecified"))
      (node (ref "R30") (pin "1") (pinfunction "1_1") (pintype "unspecified"))
    )
    (net (code "55") (name "Net-(Q1-C)") (class "Default")
      (node (ref "Q1") (pin "3") (pinfunction "C_3") (pintype "unspecified"))
      (node (ref "R28") (pin "1") (pinfunction "1_1") (pintype "unspecified"))
    )
    (net (code "56") (name "Net-(Q2-B)") (class "Default")
      (node (ref "Q2") (pin "1") (pinfunction "B_1") (pintype "unspecified"))
      (node (ref "R32") (pin "2") (pinfunction "2_2") (pintype "unspecified"))
      (node (ref "R33") (pin "1") (pinfunction "1_1") (pintype "unspecified"))
    )
    (net (code "57") (name "Net-(Q3-B)") (class "Default")
      (node (ref "Q3") (pin "1") (pinfunction "B_1") (pintype "unspecified"))
      (node (ref "R34") (pin "2") (pinfunction "2_2") (pintype "unspecified"))
      (node (ref "R35") (pin "1") (pinfunction "1_1") (pintype "unspecified"))
    )
    (net (code "58") (name "Net-(U6-K)") (class "Default")
      (node (ref "F3") (pin "1") (pinfunction "1_1") (pintype "input"))
      (node (ref "U6") (pin "1") (pinfunction "K_1") (pintype "unspecified"))
    )
    (net (code "59") (name "RF_D0") (class "Default")
      (node (ref "P9") (pin "3") (pinfunction "3_3") (pintype "input"))
      (node (ref "R20") (pin "2") (pinfunction "2_2") (pintype "unspecified"))
    )
    (net (code "60") (name "RF_D1") (class "Default")
      (node (ref "P9") (pin "4") (pinfunction "4_4") (pintype "input"))
      (node (ref "R21") (pin "2") (pinfunction "2_2") (pintype "unspecified"))
    )
    (net (code "61") (name "RF_D2") (class "Default")
      (node (ref "P9") (pin "5") (pinfunction "5_5") (pintype "input"))
      (node (ref "R22") (pin "2") (pinfunction "2_2") (pintype "unspecified"))
    )
    (net (code "62") (name "RF_D3") (class "Default")
      (node (ref "P9") (pin "6") (pinfunction "6_6") (pintype "input"))
      (node (ref "R23") (pin "2") (pinfunction "2_2") (pintype "unspecified"))
    )
    (net (code "63") (name "SWCLK") (class "Default")
      (node (ref "U1") (pin "24") (pinfunction "PA14(SWCLK)_24") (pintype "bidirectional"))
      (node (ref "U2") (pin "2") (pinfunction "2_2") (pintype "unspecified"))
    )
    (net (code "64") (name "SWDIO") (class "Default")
      (node (ref "U1") (pin "23") (pinfunction "PA13(SWDIO)_23") (pintype "bidirectional"))
      (node (ref "U2") (pin "4") (pinfunction "4_4") (pintype "unspecified"))
    )
    (net (code "65") (name "SWITCH") (class "Default")
      (node (ref "P5") (pin "1") (pinfunction "1_1") (pintype "input"))
      (node (ref "R11") (pin "1") (pinfunction "1_1") (pintype "unspecified"))
    )
    (net (code "66") (name "VCC") (class "Default")
      (node (ref "C1") (pin "2") (pinfunction "2_2") (pintype "input"))
      (node (ref "C10") (pin "2") (pinfunction "2_2") (pintype "input"))
      (node (ref "C2") (pin "2") (pinfunction "2_2") (pintype "input"))
      (node (ref "C3") (pin "2") (pinfunction "2_2") (pintype "input"))
      (node (ref "C4") (pin "2") (pinfunction "2_2") (pintype "input"))
      (node (ref "C5") (pin "2") (pinfunction "2_2") (pintype "input"))
      (node (ref "C6") (pin "2") (pinfunction "2_2") (pintype "input"))
      (node (ref "C7") (pin "2") (pinfunction "2_2") (pintype "input"))
      (node (ref "C8") (pin "2") (pinfunction "2_2") (pintype "input"))
      (node (ref "C9") (pin "2") (pinfunction "2_2") (pintype "input"))
      (node (ref "D11") (pin "2") (pinfunction "2_2") (pintype "unspecified"))
      (node (ref "D12") (pin "2") (pinfunction "2_2") (pintype "unspecified"))
      (node (ref "D2") (pin "2") (pinfunction "2_2") (pintype "unspecified"))
      (node (ref "D4") (pin "2") (pinfunction "2_2") (pintype "unspecified"))
      (node (ref "D6") (pin "2") (pinfunction "2_2") (pintype "unspecified"))
      (node (ref "D8") (pin "2") (pinfunction "2_2") (pintype "unspecified"))
      (node (ref "D9") (pin "2") (pinfunction "2_2") (pintype "unspecified"))
      (node (ref "LDO1") (pin "5") (pinfunction "VOUT_5") (pintype "input"))
      (node (ref "LED1") (pin "1") (pinfunction "A_1") (pintype "unspecified"))
      (node (ref "LED2") (pin "2") (pinfunction "A_2") (pintype "unspecified"))
      (node (ref "LED3") (pin "2") (pinfunction "A_2") (pintype "unspecified"))
      (node (ref "P9") (pin "2") (pinfunction "2_2") (pintype "input"))
      (node (ref "R24") (pin "2") (pinfunction "2_2") (pintype "unspecified"))
      (node (ref "R27") (pin "1") (pinfunction "1_1") (pintype "unspecified"))
      (node (ref "U1") (pin "1") (pinfunction "VDD_1") (pintype "unspecified"))
      (node (ref "U1") (pin "17") (pinfunction "VDD_17") (pintype "unspecified"))
      (node (ref "U1") (pin "5") (pinfunction "VDDA_5") (pintype "unspecified"))
      (node (ref "U2") (pin "1") (pinfunction "1_1") (pintype "unspecified"))
    )
    (net (code "67") (name "WDOG_LED") (class "Default")
      (node (ref "R15") (pin "1") (pinfunction "1_1") (pintype "unspecified"))
      (node (ref "U1") (pin "30") (pinfunction "PB7_30") (pintype "bidirectional"))
    )
    (net (code "68") (name "ZONE_1") (class "Default")
      (node (ref "P1") (pin "1") (pinfunction "1_1") (pintype "input"))
      (node (ref "R1") (pin "1") (pinfunction "1_1") (pintype "unspecified"))
    )
    (net (code "69") (name "ZONE_2") (class "Default")
      (node (ref "P1") (pin "3") (pinfunction "3_3") (pintype "input"))
      (node (ref "R3") (pin "1") (pinfunction "1_1") (pintype "unspecified"))
    )
    (net (code "70") (name "ZONE_3") (class "Default")
      (node (ref "P2") (pin "1") (pinfunction "1_1") (pintype "input"))
      (node (ref "R5") (pin "1") (pinfunction "1_1") (pintype "unspecified"))
    )
    (net (code "71") (name "ZONE_4") (class "Default")
      (node (ref "P2") (pin "3") (pinfunction "3_3") (pintype "input"))
      (node (ref "R7") (pin "1") (pinfunction "1_1") (pintype "unspecified"))
    )
    (net (code "72") (name "ZONE_STATUS") (class "Default")
      (node (ref "P4") (pin "1") (pinfunction "1_1") (pintype "unspecified"))
      (node (ref "R13") (pin "1") (pinfunction "1_1") (pintype "unspecified"))
    )
    (net (code "73") (name "unconnected-(LDO1-NC-Pad4)") (class "Default")
      (node (ref "LDO1") (pin "4") (pinfunction "NC_4") (pintype "input"))
    )
  )
)
